# W5500.net
KiCad netlist of a schematic drawn in Altium Designer
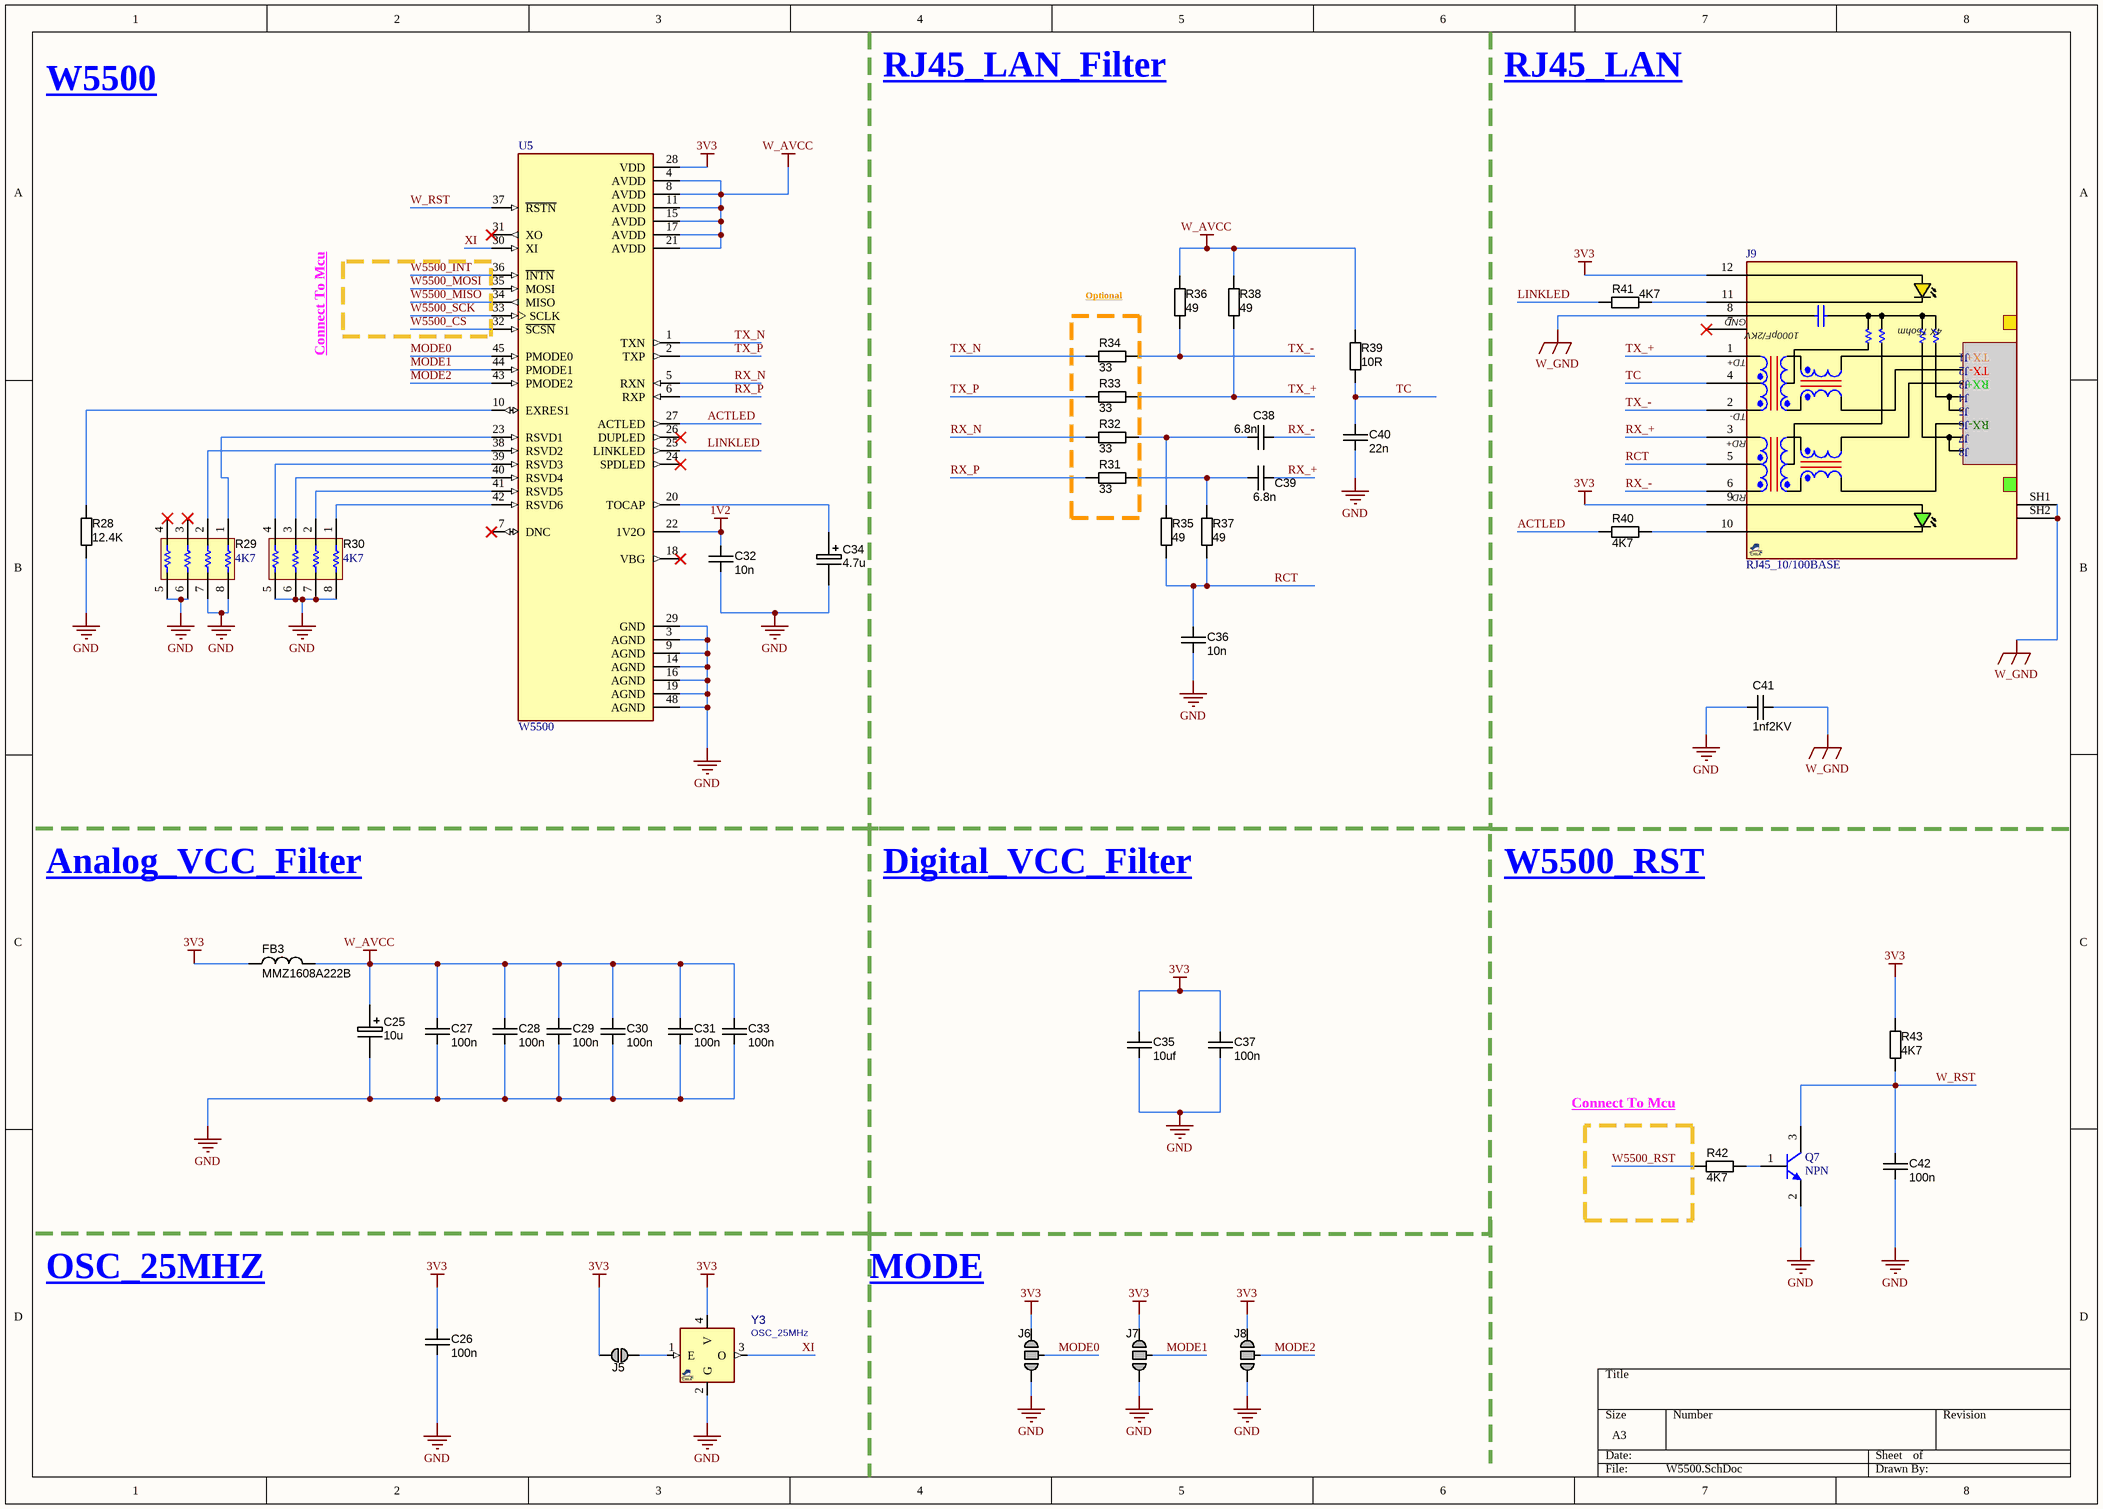
[diagram p0: W5500.SchDoc]

(export (version "E")
  (design (tool "Eeschema 10.0.6"))
  (components
    (comp (ref "C25")
      (value "10u")
      (footprint "C_TN_3216")
      (description "Capacitor SMD Tantalum 10uF 10% 16V 3216-18")
      (fields (field (name "TOLERANCE") "±10%"))
      (libsource (lib "PBL - Capacitors") (part "CAPT_4u7_3216_16V"))
    )
    (comp (ref "C26")
      (value "100n")
      (footprint "CAPC1608X90N")
      (description "Capacitor SMD Cer 100nF 10% 50V X7R 0603")
      (fields (field (name "TOLERANCE") "±10%") (field (name "Comment") "approved sub OK"))
      (libsource (lib "PBL - Capacitors") (part "CAPC_100n_0603_X7R_50V_10%"))
    )
    (comp (ref "C27")
      (value "100n")
      (footprint "CAPC1608X90N")
      (description "Capacitor SMD Cer 100nF 10% 50V X7R 0603")
      (fields (field (name "TOLERANCE") "±10%") (field (name "Comment") "approved sub OK"))
      (libsource (lib "PBL - Capacitors") (part "CAPC_100n_0603_X7R_50V_10%"))
    )
    (comp (ref "C28")
      (value "100n")
      (footprint "CAPC1608X90N")
      (description "Capacitor SMD Cer 100nF 10% 50V X7R 0603")
      (fields (field (name "TOLERANCE") "±10%") (field (name "Comment") "approved sub OK"))
      (libsource (lib "PBL - Capacitors") (part "CAPC_100n_0603_X7R_50V_10%"))
    )
    (comp (ref "C29")
      (value "100n")
      (footprint "CAPC1608X90N")
      (description "Capacitor SMD Cer 100nF 10% 50V X7R 0603")
      (fields (field (name "TOLERANCE") "±10%") (field (name "Comment") "approved sub OK"))
      (libsource (lib "PBL - Capacitors") (part "CAPC_100n_0603_X7R_50V_10%"))
    )
    (comp (ref "C30")
      (value "100n")
      (footprint "CAPC1608X90N")
      (description "Capacitor SMD Cer 100nF 10% 50V X7R 0603")
      (fields (field (name "TOLERANCE") "±10%") (field (name "Comment") "approved sub OK"))
      (libsource (lib "PBL - Capacitors") (part "CAPC_100n_0603_X7R_50V_10%"))
    )
    (comp (ref "C31")
      (value "100n")
      (footprint "CAPC1608X90N")
      (description "Capacitor SMD Cer 100nF 10% 50V X7R 0603")
      (fields (field (name "TOLERANCE") "±10%") (field (name "Comment") "approved sub OK"))
      (libsource (lib "PBL - Capacitors") (part "CAPC_100n_0603_X7R_50V_10%"))
    )
    (comp (ref "C32")
      (value "10n")
      (footprint "CAPC1608X90N")
      (description "Capacitor SMD Cer 10nF 10% 50V X7R 0603")
      (fields (field (name "TOLERANCE") "±10%") (field (name "Comment") "approved sub OK"))
      (libsource (lib "PBL - Capacitors") (part "CAPC_100n_0603_X7R_50V_10%"))
    )
    (comp (ref "C33")
      (value "100n")
      (footprint "CAPC1608X90N")
      (description "Capacitor SMD Cer 100nF 10% 50V X7R 0603")
      (fields (field (name "TOLERANCE") "±10%") (field (name "Comment") "approved sub OK"))
      (libsource (lib "PBL - Capacitors") (part "CAPC_100n_0603_X7R_50V_10%"))
    )
    (comp (ref "C34")
      (value "4.7u")
      (footprint "C_TN_3216")
      (description "Capacitor SMD Tantalum 4.7uF 10% 16V 3216-18")
      (fields (field (name "TOLERANCE") "±10%"))
      (libsource (lib "PBL - Capacitors") (part "CAPT_4u7_3216_16V"))
    )
    (comp (ref "C35")
      (value "10uf")
      (footprint "CAPC1608X90N")
      (description "Capacitor SMD Cer 100nF 10% 50V X7R 0603")
      (fields (field (name "TOLERANCE") "±10%") (field (name "Comment") "approved sub OK"))
      (libsource (lib "PBL - Capacitors") (part "CAPC_100n_0603_X7R_50V_10%"))
    )
    (comp (ref "C36")
      (value "10n")
      (footprint "CAPC1608X90N")
      (description "Capacitor SMD Cer 100nF 10% 50V X7R 0603")
      (fields (field (name "TOLERANCE") "±10%") (field (name "Comment") "approved sub OK"))
      (libsource (lib "PBL - Capacitors") (part "CAPC_100n_0603_X7R_50V_10%"))
    )
    (comp (ref "C37")
      (value "100n")
      (footprint "CAPC1608X90N")
      (description "Capacitor SMD Cer 100nF 10% 50V X7R 0603")
      (fields (field (name "TOLERANCE") "±10%") (field (name "Comment") "approved sub OK"))
      (libsource (lib "PBL - Capacitors") (part "CAPC_100n_0603_X7R_50V_10%"))
    )
    (comp (ref "C38")
      (value "6.8n")
      (footprint "CAPC1608X90N")
      (description "Capacitor SMD Cer 6.8 10% 50V X7R 0603")
      (fields (field (name "TOLERANCE") "±10%") (field (name "Comment") "approved sub OK"))
      (libsource (lib "PBL - Capacitors") (part "CAPC_100n_0603_X7R_50V_10%"))
    )
    (comp (ref "C39")
      (value "6.8n")
      (footprint "CAPC1608X90N")
      (description "Capacitor SMD Cer 6.8nf 10% 50V X7R 0603")
      (fields (field (name "TOLERANCE") "±10%") (field (name "Comment") "approved sub OK"))
      (libsource (lib "PBL - Capacitors") (part "CAPC_100n_0603_X7R_50V_10%"))
    )
    (comp (ref "C40")
      (value "22n")
      (footprint "CAPC1608X90N")
      (description "Capacitor SMD Cer 100nF 10% 50V X7R 0603")
      (fields (field (name "TOLERANCE") "±10%") (field (name "Comment") "approved sub OK"))
      (libsource (lib "PBL - Capacitors") (part "CAPC_100n_0603_X7R_50V_10%"))
    )
    (comp (ref "C41")
      (value "1nf2KV")
      (footprint "C1206")
      (description "Capacitor SMD Cer 1nF 10% 2kv X7R 0603")
      (fields (field (name "TOLERANCE") "±10%") (field (name "Comment") "approved sub OK"))
      (libsource (lib "PBL - Capacitors") (part "CAPC_100n_0603_X7R_50V_10%"))
    )
    (comp (ref "C42")
      (value "100n")
      (footprint "CAPC1608X90N")
      (description "Capacitor SMD Cer 100nF 10% 50V X7R 0603")
      (fields (field (name "TOLERANCE") "±10%") (field (name "Comment") "approved sub OK"))
      (libsource (lib "PBL - Capacitors") (part "CAPC_100n_0603_X7R_50V_10%"))
    )
    (comp (ref "FB3")
      (value "2K2 @ 100 MHz")
      (footprint "FBC1608X95N")
      (description "Ferrite bead 2.2K Ohm at 100 MHz 200mA 0603 SMD")
      (fields (field (name "MANUFACTURER PART NUMBER 1") "MMZ1608A222B"))
      (libsource (lib "PBL - Inductors") (part "FERRITE_2K2-100MHz_0603"))
    )
    (comp (ref "J5")
      (value "Jumper")
      (footprint "JUMP1")
      (description "SMD jumper")
      (libsource (lib "PBL - Pads and Jumpers") (part "JUMP1"))
    )
    (comp (ref "J6")
      (value "Jumper")
      (footprint "Jump_3Way")
      (description "SMD jumper")
      (libsource (lib "PBL - Pads and Jumpers") (part "JUMP_3WAY"))
    )
    (comp (ref "J7")
      (value "Jumper")
      (footprint "Jump_3Way")
      (description "SMD jumper")
      (libsource (lib "PBL - Pads and Jumpers") (part "JUMP_3WAY"))
    )
    (comp (ref "J8")
      (value "Jumper")
      (footprint "Jump_3Way")
      (description "SMD jumper")
      (libsource (lib "PBL - Pads and Jumpers") (part "JUMP_3WAY"))
    )
    (comp (ref "J9")
      (value "RJ45_10/100BASE")
      (footprint "RJ45_8M_HR911105A")
      (description "RJ45, 10/100BASE, G/Y LED")
      (fields (field (name "MANF") "Hanrun") (field (name "MANF_P#") "HR911105A"))
      (libsource (lib "conn_rj_ModularJack") (part "RJ45_HR911105A"))
    )
    (comp (ref "Q7")
      (value "NPN")
      (footprint "SOT23-3")
      (description "NPN Bipolar Transistor")
      (fields (field (name "PUBLISHER") "Altium Limited"))
      (libsource (lib "Miscellaneous Devices") (part "NPN"))
    )
    (comp (ref "R28")
      (value "12.4K")
      (footprint "RESC1608X55N")
      (description "Resistor SMD chip 12.4K Ohm 0.1W 1% 0603")
      (fields (field (name "TOLERANCE") "±5%") (field (name "Comment") "Thick Film"))
      (libsource (lib "PBL - Resistors") (part "RES_4K7_0603_5%"))
    )
    (comp (ref "R29")
      (value "4K7")
      (footprint "RP0603X4")
      (description "Resistor Array SMD")
      (libsource (lib "Resistor") (part "Resistor Array SMD"))
    )
    (comp (ref "R30")
      (value "4K7")
      (footprint "RP0603X4")
      (description "Resistor Array SMD")
      (libsource (lib "Resistor") (part "Resistor Array SMD"))
    )
    (comp (ref "R31")
      (value "33")
      (footprint "RESC1608X55N")
      (description "Resistor SMD chip 33 Ohm 0.1W 5% 0603")
      (fields (field (name "TOLERANCE") "±5%") (field (name "Comment") "Thick Film"))
      (libsource (lib "PBL - Resistors") (part "RES_4K7_0603_5%"))
    )
    (comp (ref "R32")
      (value "33")
      (footprint "RESC1608X55N")
      (description "Resistor SMD chip 33 Ohm 0.1W 5% 0603")
      (fields (field (name "TOLERANCE") "±5%") (field (name "Comment") "Thick Film"))
      (libsource (lib "PBL - Resistors") (part "RES_4K7_0603_5%"))
    )
    (comp (ref "R33")
      (value "33")
      (footprint "RESC1608X55N")
      (description "Resistor SMD chip 33 Ohm 0.1W 5% 0603")
      (fields (field (name "TOLERANCE") "±5%") (field (name "Comment") "Thick Film"))
      (libsource (lib "PBL - Resistors") (part "RES_4K7_0603_5%"))
    )
    (comp (ref "R34")
      (value "33")
      (footprint "RESC1608X55N")
      (description "Resistor SMD chip 33 Ohm 0.1W 5% 0603")
      (fields (field (name "TOLERANCE") "±5%") (field (name "Comment") "Thick Film"))
      (libsource (lib "PBL - Resistors") (part "RES_4K7_0603_5%"))
    )
    (comp (ref "R35")
      (value "49")
      (footprint "RESC1608X55N")
      (description "Resistor SMD chip 49 Ohm 0.1W 5% 0603")
      (fields (field (name "TOLERANCE") "±5%") (field (name "Comment") "Thick Film"))
      (libsource (lib "") (part "RES_4K7_0603_5%_1"))
    )
    (comp (ref "R36")
      (value "49")
      (footprint "RESC1608X55N")
      (description "Resistor SMD chip 49 Ohm 0.1W 5% 0603")
      (fields (field (name "TOLERANCE") "±5%") (field (name "Comment") "Thick Film"))
      (libsource (lib "") (part "RES_4K7_0603_5%_1"))
    )
    (comp (ref "R37")
      (value "49")
      (footprint "RESC1608X55N")
      (description "Resistor SMD chip 49 Ohm 0.1W 5% 0603")
      (fields (field (name "TOLERANCE") "±5%") (field (name "Comment") "Thick Film"))
      (libsource (lib "") (part "RES_4K7_0603_5%_1"))
    )
    (comp (ref "R38")
      (value "49")
      (footprint "RESC1608X55N")
      (description "Resistor SMD chip 49 Ohm 0.1W 5% 0603")
      (fields (field (name "TOLERANCE") "±5%") (field (name "Comment") "Thick Film"))
      (libsource (lib "") (part "RES_4K7_0603_5%_1"))
    )
    (comp (ref "R39")
      (value "10R")
      (footprint "RESC1608X55N")
      (description "Resistor SMD chip 10 Ohm 0.1W 5% 0603")
      (fields (field (name "TOLERANCE") "±5%") (field (name "Comment") "Thick Film"))
      (libsource (lib "") (part "RES_4K7_0603_5%_1"))
    )
    (comp (ref "R40")
      (value "4K7")
      (footprint "RESC1608X55N")
      (description "Resistor SMD chip 4.7k Ohm 0.1W 5% 0603")
      (fields (field (name "TOLERANCE") "±5%") (field (name "Comment") "Thick Film"))
      (libsource (lib "PBL - Resistors") (part "RES_4K7_0603_5%"))
    )
    (comp (ref "R41")
      (value "4K7")
      (footprint "RESC1608X55N")
      (description "Resistor SMD chip 4.7k Ohm 0.1W 5% 0603")
      (fields (field (name "TOLERANCE") "±5%") (field (name "Comment") "Thick Film"))
      (libsource (lib "PBL - Resistors") (part "RES_4K7_0603_5%"))
    )
    (comp (ref "R42")
      (value "4K7")
      (footprint "RESC1608X55N")
      (description "Resistor SMD chip 4.7k Ohm 0.1W 5% 0603")
      (fields (field (name "TOLERANCE") "±5%") (field (name "Comment") "Thick Film"))
      (libsource (lib "") (part "RES_4K7_0603_5%_1"))
    )
    (comp (ref "R43")
      (value "4K7")
      (footprint "RESC1608X55N")
      (description "Resistor SMD chip 4.7k Ohm 0.1W 5% 0603")
      (fields (field (name "TOLERANCE") "±5%") (field (name "Comment") "Thick Film"))
      (libsource (lib "") (part "RES_4K7_0603_5%_2"))
    )
    (comp (ref "U5")
      (value "W5500")
      (footprint "LQFP-48_N")
      (description "Socket Contact Silver 17-20 AWG Crimp Power")
      (fields (field (name "MF") "WIZnet"))
      (libsource (lib "W5500") (part "W5500"))
    )
    (comp (ref "Y3")
      (value "OSC_25MHz")
      (footprint "XTL_4_2520")
      (description "CLOCK OSCILLATOR, 25MHz, 10PPM, 3.2X2.5mm")
      (fields (field (name "MANF") "ECS") (field (name "MANF_P#") "ECS-3225S18-250-FN-TR"))
      (libsource (lib "crystal_osc") (part "OSC_4_25MHz_3225E"))
    )
  )
  (nets
    (net (code "1") (name "/ACTLED") (class "Default")
      (node (ref "R40") (pin "1") (pinfunction "1_1") (pintype "passive"))
      (node (ref "U5") (pin "27") (pinfunction "ACTLED_27") (pintype "output"))
    )
    (net (code "2") (name "/LINKLED") (class "Default")
      (node (ref "R41") (pin "1") (pinfunction "1_1") (pintype "passive"))
      (node (ref "U5") (pin "25") (pinfunction "LINKLED_25") (pintype "output"))
    )
    (net (code "3") (name "/MODE0") (class "Default")
      (node (ref "J6") (pin "2") (pinfunction "2_2") (pintype "passive"))
      (node (ref "U5") (pin "45") (pinfunction "PMODE0_45") (pintype "input"))
    )
    (net (code "4") (name "/MODE1") (class "Default")
      (node (ref "J7") (pin "2") (pinfunction "2_2") (pintype "passive"))
      (node (ref "U5") (pin "44") (pinfunction "PMODE1_44") (pintype "input"))
    )
    (net (code "5") (name "/MODE2") (class "Default")
      (node (ref "J8") (pin "2") (pinfunction "2_2") (pintype "passive"))
      (node (ref "U5") (pin "43") (pinfunction "PMODE2_43") (pintype "input"))
    )
    (net (code "6") (name "/RCT") (class "Default")
      (node (ref "C36") (pin "1") (pintype "passive"))
      (node (ref "J9") (pin "5") (pinfunction "RCT_5") (pintype "passive"))
      (node (ref "R35") (pin "1") (pinfunction "1_1") (pintype "passive"))
      (node (ref "R37") (pin "1") (pinfunction "1_1") (pintype "passive"))
    )
    (net (code "7") (name "/RX_+") (class "Default")
      (node (ref "C39") (pin "2") (pintype "passive"))
      (node (ref "J9") (pin "3") (pinfunction "RD+_3") (pintype "passive"))
    )
    (net (code "8") (name "/RX_-") (class "Default")
      (node (ref "C38") (pin "2") (pintype "passive"))
      (node (ref "J9") (pin "6") (pinfunction "RD-_6") (pintype "passive"))
    )
    (net (code "9") (name "/RX_N") (class "Default")
      (node (ref "R32") (pin "1") (pinfunction "1_1") (pintype "passive"))
      (node (ref "U5") (pin "5") (pinfunction "RXN_5") (pintype "input"))
    )
    (net (code "10") (name "/RX_P") (class "Default")
      (node (ref "R31") (pin "1") (pinfunction "1_1") (pintype "passive"))
      (node (ref "U5") (pin "6") (pinfunction "RXP_6") (pintype "input"))
    )
    (net (code "11") (name "/TC") (class "Default")
      (node (ref "C40") (pin "1") (pintype "passive"))
      (node (ref "J9") (pin "4") (pinfunction "TCT_4") (pintype "passive"))
      (node (ref "R39") (pin "1") (pinfunction "1_1") (pintype "passive"))
    )
    (net (code "12") (name "/TX_+") (class "Default")
      (node (ref "J9") (pin "1") (pinfunction "TD+_1") (pintype "passive"))
      (node (ref "R33") (pin "2") (pinfunction "2_2") (pintype "passive"))
      (node (ref "R38") (pin "1") (pinfunction "1_1") (pintype "passive"))
    )
    (net (code "13") (name "/TX_-") (class "Default")
      (node (ref "J9") (pin "2") (pinfunction "TD-_2") (pintype "passive"))
      (node (ref "R34") (pin "2") (pinfunction "2_2") (pintype "passive"))
      (node (ref "R36") (pin "1") (pinfunction "1_1") (pintype "passive"))
    )
    (net (code "14") (name "/TX_N") (class "Default")
      (node (ref "R34") (pin "1") (pinfunction "1_1") (pintype "passive"))
      (node (ref "U5") (pin "1") (pinfunction "TXN_1") (pintype "output"))
    )
    (net (code "15") (name "/TX_P") (class "Default")
      (node (ref "R33") (pin "1") (pinfunction "1_1") (pintype "passive"))
      (node (ref "U5") (pin "2") (pinfunction "TXP_2") (pintype "output"))
    )
    (net (code "16") (name "/W5500_CS") (class "Default")
      (node (ref "U5") (pin "32") (pinfunction "~{SCSN}_32") (pintype "input"))
    )
    (net (code "17") (name "/W5500_INT") (class "Default")
      (node (ref "U5") (pin "36") (pinfunction "~{INTN}_36") (pintype "input"))
    )
    (net (code "18") (name "/W5500_MISO") (class "Default")
      (node (ref "U5") (pin "34") (pinfunction "MISO_34") (pintype "output"))
    )
    (net (code "19") (name "/W5500_MOSI") (class "Default")
      (node (ref "U5") (pin "35") (pinfunction "MOSI_35") (pintype "input"))
    )
    (net (code "20") (name "/W5500_RST") (class "Default")
      (node (ref "R42") (pin "1") (pinfunction "1_1") (pintype "passive"))
    )
    (net (code "21") (name "/W5500_SCK") (class "Default")
      (node (ref "U5") (pin "33") (pinfunction "SCLK_33") (pintype "input"))
    )
    (net (code "22") (name "/W_RST") (class "Default")
      (node (ref "C42") (pin "1") (pintype "passive"))
      (node (ref "Q7") (pin "3") (pinfunction "C_3") (pintype "passive"))
      (node (ref "R43") (pin "2") (pinfunction "2_2") (pintype "passive"))
      (node (ref "U5") (pin "37") (pinfunction "~{RSTN}_37") (pintype "input"))
    )
    (net (code "23") (name "/XI") (class "Default")
      (node (ref "U5") (pin "30") (pinfunction "XI_30") (pintype "input"))
      (node (ref "Y3") (pin "3") (pinfunction "O_3") (pintype "output"))
    )
    (net (code "24") (name "1V2") (class "Default")
      (node (ref "C32") (pin "1") (pintype "passive"))
      (node (ref "U5") (pin "22") (pinfunction "1V2O_22") (pintype "power_in"))
    )
    (net (code "25") (name "3V3") (class "Default")
      (node (ref "C26") (pin "1") (pintype "passive"))
      (node (ref "C35") (pin "1") (pintype "passive"))
      (node (ref "C37") (pin "1") (pintype "passive"))
      (node (ref "FB3") (pin "1") (pinfunction "1_1") (pintype "passive"))
      (node (ref "J5") (pin "2") (pintype "passive"))
      (node (ref "J6") (pin "3") (pinfunction "3_3") (pintype "passive"))
      (node (ref "J7") (pin "3") (pinfunction "3_3") (pintype "passive"))
      (node (ref "J8") (pin "3") (pinfunction "3_3") (pintype "passive"))
      (node (ref "J9") (pin "12") (pinfunction "YLED+_12") (pintype "passive"))
      (node (ref "J9") (pin "9") (pinfunction "GLED+_9") (pintype "passive"))
      (node (ref "R43") (pin "1") (pinfunction "1_1") (pintype "passive"))
      (node (ref "U5") (pin "28") (pinfunction "VDD_28") (pintype "power_in"))
      (node (ref "Y3") (pin "4") (pinfunction "V_4") (pintype "power_in"))
    )
    (net (code "26") (name "GND") (class "Default")
      (node (ref "C25") (pin "2") (pintype "passive"))
      (node (ref "C26") (pin "2") (pintype "passive"))
      (node (ref "C27") (pin "2") (pintype "passive"))
      (node (ref "C28") (pin "2") (pintype "passive"))
      (node (ref "C29") (pin "2") (pintype "passive"))
      (node (ref "C30") (pin "2") (pintype "passive"))
      (node (ref "C31") (pin "2") (pintype "passive"))
      (node (ref "C32") (pin "2") (pintype "passive"))
      (node (ref "C33") (pin "2") (pintype "passive"))
      (node (ref "C34") (pin "2") (pintype "passive"))
      (node (ref "C35") (pin "2") (pintype "passive"))
      (node (ref "C36") (pin "2") (pintype "passive"))
      (node (ref "C37") (pin "2") (pintype "passive"))
      (node (ref "C40") (pin "2") (pintype "passive"))
      (node (ref "C41") (pin "1") (pintype "passive"))
      (node (ref "C42") (pin "2") (pintype "passive"))
      (node (ref "J6") (pin "1") (pinfunction "1_1") (pintype "passive"))
      (node (ref "J7") (pin "1") (pinfunction "1_1") (pintype "passive"))
      (node (ref "J8") (pin "1") (pinfunction "1_1") (pintype "passive"))
      (node (ref "Q7") (pin "2") (pinfunction "E_2") (pintype "passive"))
      (node (ref "R28") (pin "1") (pinfunction "1_1") (pintype "passive"))
      (node (ref "R29") (pin "5") (pinfunction "5_5") (pintype "passive"))
      (node (ref "R29") (pin "6") (pinfunction "6_6") (pintype "passive"))
      (node (ref "R29") (pin "7") (pinfunction "7_7") (pintype "passive"))
      (node (ref "R29") (pin "8") (pinfunction "8_8") (pintype "passive"))
      (node (ref "R30") (pin "5") (pinfunction "5_5") (pintype "passive"))
      (node (ref "R30") (pin "6") (pinfunction "6_6") (pintype "passive"))
      (node (ref "R30") (pin "7") (pinfunction "7_7") (pintype "passive"))
      (node (ref "R30") (pin "8") (pinfunction "8_8") (pintype "passive"))
      (node (ref "U5") (pin "14") (pinfunction "AGND_14") (pintype "power_in"))
      (node (ref "U5") (pin "16") (pinfunction "AGND_16") (pintype "power_in"))
      (node (ref "U5") (pin "19") (pinfunction "AGND_19") (pintype "power_in"))
      (node (ref "U5") (pin "29") (pinfunction "GND_29") (pintype "passive"))
      (node (ref "U5") (pin "3") (pinfunction "AGND_3") (pintype "power_in"))
      (node (ref "U5") (pin "48") (pinfunction "AGND_48") (pintype "power_in"))
      (node (ref "U5") (pin "9") (pinfunction "AGND_9") (pintype "power_in"))
      (node (ref "Y3") (pin "2") (pinfunction "G_2") (pintype "power_in"))
    )
    (net (code "27") (name "Net-(C38-Pad1)") (class "Default")
      (node (ref "C38") (pin "1") (pintype "passive"))
      (node (ref "R32") (pin "2") (pinfunction "2_2") (pintype "passive"))
      (node (ref "R35") (pin "2") (pinfunction "2_2") (pintype "passive"))
    )
    (net (code "28") (name "Net-(C39-Pad1)") (class "Default")
      (node (ref "C39") (pin "1") (pintype "passive"))
      (node (ref "R31") (pin "2") (pinfunction "2_2") (pintype "passive"))
      (node (ref "R37") (pin "2") (pinfunction "2_2") (pintype "passive"))
    )
    (net (code "29") (name "Net-(J9-GLED-)") (class "Default")
      (node (ref "J9") (pin "10") (pinfunction "GLED-_10") (pintype "passive"))
      (node (ref "R40") (pin "2") (pinfunction "2_2") (pintype "passive"))
    )
    (net (code "30") (name "Net-(J9-YLED-)") (class "Default")
      (node (ref "J9") (pin "11") (pinfunction "YLED-_11") (pintype "passive"))
      (node (ref "R41") (pin "2") (pinfunction "2_2") (pintype "passive"))
    )
    (net (code "31") (name "Net-(Q7-B)") (class "Default")
      (node (ref "Q7") (pin "1") (pinfunction "B_1") (pintype "passive"))
      (node (ref "R42") (pin "2") (pinfunction "2_2") (pintype "passive"))
    )
    (net (code "32") (name "Net-(U5-EXRES1)") (class "Default")
      (node (ref "R28") (pin "2") (pinfunction "2_2") (pintype "passive"))
      (node (ref "U5") (pin "10") (pinfunction "EXRES1_10") (pintype "bidirectional"))
    )
    (net (code "33") (name "Net-(U5-RSVD1)") (class "Default")
      (node (ref "R29") (pin "1") (pinfunction "1_1") (pintype "passive"))
      (node (ref "U5") (pin "23") (pinfunction "RSVD1_23") (pintype "input"))
    )
    (net (code "34") (name "Net-(U5-RSVD2)") (class "Default")
      (node (ref "R29") (pin "2") (pinfunction "2_2") (pintype "passive"))
      (node (ref "U5") (pin "38") (pinfunction "RSVD2_38") (pintype "input"))
    )
    (net (code "35") (name "Net-(U5-RSVD3)") (class "Default")
      (node (ref "R30") (pin "4") (pinfunction "4_4") (pintype "passive"))
      (node (ref "U5") (pin "39") (pinfunction "RSVD3_39") (pintype "input"))
    )
    (net (code "36") (name "Net-(U5-RSVD4)") (class "Default")
      (node (ref "R30") (pin "3") (pinfunction "3_3") (pintype "passive"))
      (node (ref "U5") (pin "40") (pinfunction "RSVD4_40") (pintype "input"))
    )
    (net (code "37") (name "Net-(U5-RSVD5)") (class "Default")
      (node (ref "R30") (pin "2") (pinfunction "2_2") (pintype "passive"))
      (node (ref "U5") (pin "41") (pinfunction "RSVD5_41") (pintype "input"))
    )
    (net (code "38") (name "Net-(U5-RSVD6)") (class "Default")
      (node (ref "R30") (pin "1") (pinfunction "1_1") (pintype "passive"))
      (node (ref "U5") (pin "42") (pinfunction "RSVD6_42") (pintype "input"))
    )
    (net (code "39") (name "Net-(U5-TOCAP)") (class "Default")
      (node (ref "C34") (pin "1") (pintype "passive"))
      (node (ref "U5") (pin "20") (pinfunction "TOCAP_20") (pintype "output"))
    )
    (net (code "40") (name "Net-(Y3-E)") (class "Default")
      (node (ref "J5") (pin "1") (pintype "passive"))
      (node (ref "Y3") (pin "1") (pinfunction "E_1") (pintype "input"))
    )
    (net (code "41") (name "W_AVCC") (class "Default")
      (node (ref "C25") (pin "1") (pintype "passive"))
      (node (ref "C27") (pin "1") (pintype "passive"))
      (node (ref "C28") (pin "1") (pintype "passive"))
      (node (ref "C29") (pin "1") (pintype "passive"))
      (node (ref "C30") (pin "1") (pintype "passive"))
      (node (ref "C31") (pin "1") (pintype "passive"))
      (node (ref "C33") (pin "1") (pintype "passive"))
      (node (ref "FB3") (pin "2") (pinfunction "2_2") (pintype "passive"))
      (node (ref "R36") (pin "2") (pinfunction "2_2") (pintype "passive"))
      (node (ref "R38") (pin "2") (pinfunction "2_2") (pintype "passive"))
      (node (ref "R39") (pin "2") (pinfunction "2_2") (pintype "passive"))
      (node (ref "U5") (pin "11") (pinfunction "AVDD_11") (pintype "power_in"))
      (node (ref "U5") (pin "15") (pinfunction "AVDD_15") (pintype "power_in"))
      (node (ref "U5") (pin "17") (pinfunction "AVDD_17") (pintype "power_in"))
      (node (ref "U5") (pin "21") (pinfunction "AVDD_21") (pintype "power_in"))
      (node (ref "U5") (pin "4") (pinfunction "AVDD_4") (pintype "power_in"))
      (node (ref "U5") (pin "8") (pinfunction "AVDD_8") (pintype "power_in"))
    )
    (net (code "42") (name "W_GND") (class "Default")
      (node (ref "C41") (pin "2") (pintype "passive"))
      (node (ref "J9") (pin "8") (pinfunction "CHSGND_8") (pintype "passive"))
      (node (ref "J9") (pin "SH1") (pinfunction "SH1_SH1") (pintype "passive"))
      (node (ref "J9") (pin "SH2") (pinfunction "SH2_SH2") (pintype "passive"))
    )
    (net (code "43") (name "unconnected-(J9-NC-Pad7)") (class "Default")
      (node (ref "J9") (pin "7") (pinfunction "NC_7") (pintype "passive+no_connect"))
    )
    (net (code "44") (name "unconnected-(R29-Pad3)") (class "Default")
      (node (ref "R29") (pin "3") (pinfunction "3_3") (pintype "passive+no_connect"))
    )
    (net (code "45") (name "unconnected-(R29-Pad4)") (class "Default")
      (node (ref "R29") (pin "4") (pinfunction "4_4") (pintype "passive+no_connect"))
    )
    (net (code "46") (name "unconnected-(U5-DNC-Pad7)") (class "Default")
      (node (ref "U5") (pin "7") (pinfunction "DNC_7") (pintype "bidirectional+no_connect"))
    )
    (net (code "47") (name "unconnected-(U5-DUPLED-Pad26)") (class "Default")
      (node (ref "U5") (pin "26") (pinfunction "DUPLED_26") (pintype "output+no_connect"))
    )
    (net (code "48") (name "unconnected-(U5-SPDLED-Pad24)") (class "Default")
      (node (ref "U5") (pin "24") (pinfunction "SPDLED_24") (pintype "output+no_connect"))
    )
    (net (code "49") (name "unconnected-(U5-VBG-Pad18)") (class "Default")
      (node (ref "U5") (pin "18") (pinfunction "VBG_18") (pintype "output+no_connect"))
    )
    (net (code "50") (name "unconnected-(U5-XO-Pad31)") (class "Default")
      (node (ref "U5") (pin "31") (pinfunction "XO_31") (pintype "output+no_connect"))
    )
  )
)
